# PowerRegulationBoardV2.net
KiCad netlist of a schematic drawn in Altium Designer
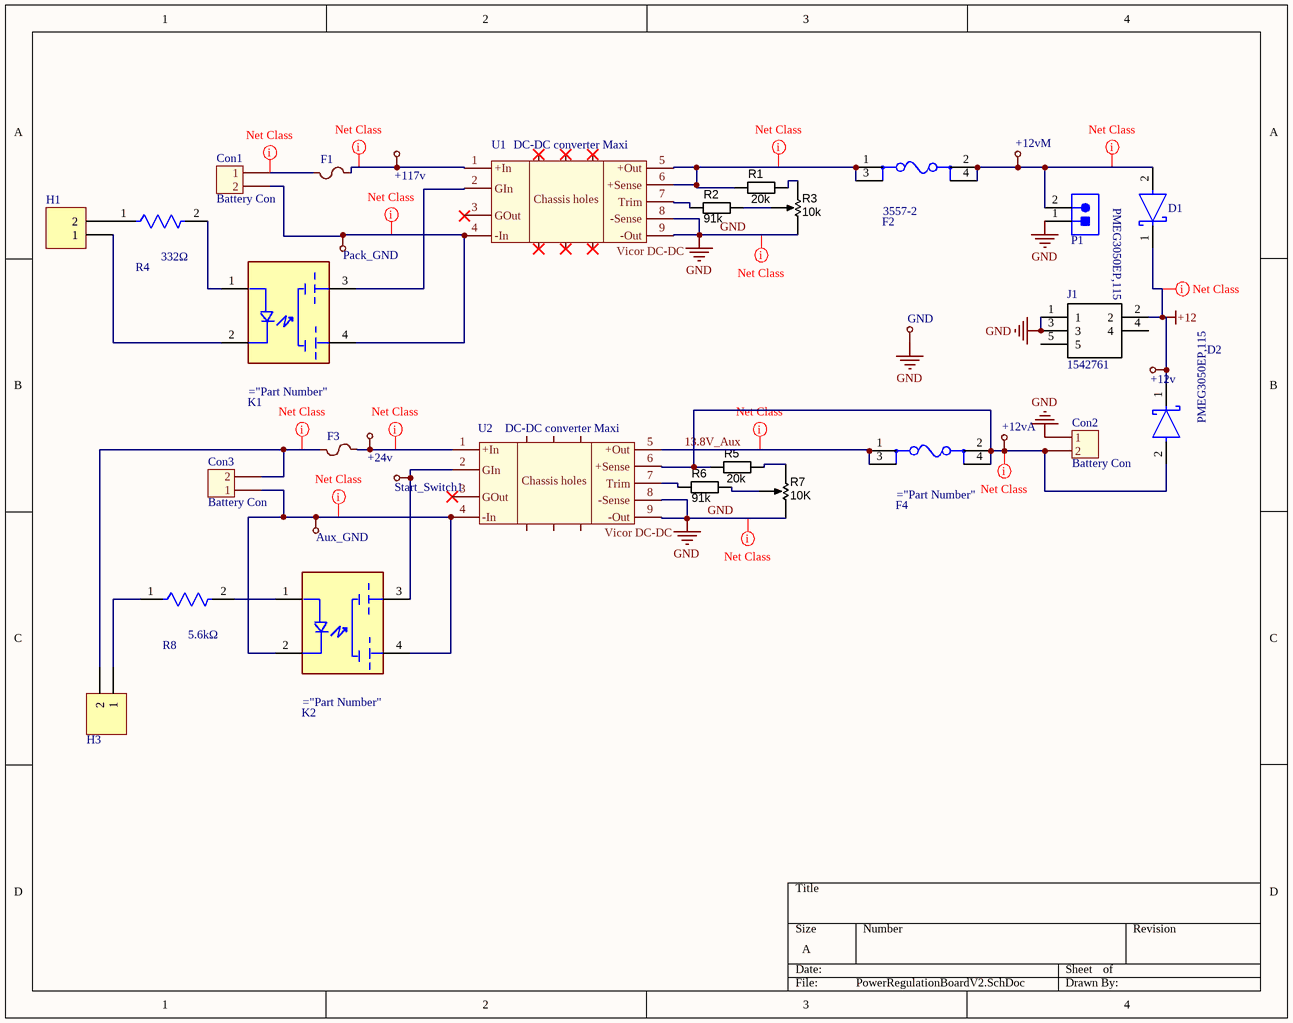
[diagram p0: PowerRegulationBoardV2.SchDoc]

(export (version "E")
  (design (tool "Eeschema 10.0.6"))
  (components
    (comp (ref "+12v")
      (value "Testpoint")
      (footprint "TestPoint")
      (libsource (lib "Components_library") (part "Testpoint"))
    )
    (comp (ref "+12vA")
      (value "Testpoint")
      (footprint "TestPoint")
      (libsource (lib "Components_library") (part "Testpoint"))
    )
    (comp (ref "+12vM")
      (value "Testpoint")
      (footprint "TestPoint")
      (libsource (lib "Components_library") (part "Testpoint"))
    )
    (comp (ref "+24v")
      (value "Testpoint")
      (footprint "TestPoint")
      (libsource (lib "Components_library") (part "Testpoint"))
    )
    (comp (ref "+117v")
      (value "Testpoint")
      (footprint "TestPoint")
      (libsource (lib "Components_library") (part "Testpoint"))
    )
    (comp (ref "Aux_GND")
      (value "Testpoint")
      (footprint "TestPoint")
      (libsource (lib "Components_library") (part "Testpoint"))
    )
    (comp (ref "Con1")
      (value "Battery Con")
      (footprint "Battery Con")
      (description "Aux and Main battery connector")
      (libsource (lib "") (part "Battery Con_1"))
    )
    (comp (ref "Con2")
      (value "Battery Con")
      (footprint "Battery Con")
      (description "Aux and Main battery connector")
      (libsource (lib "Components_library") (part "Battery Con"))
    )
    (comp (ref "Con3")
      (value "Battery Con")
      (footprint "Battery Con")
      (description "Aux and Main battery connector")
      (libsource (lib "") (part "Battery Con_1"))
    )
    (comp (ref "D1")
      (value "PMEG3050EP,115")
      (footprint "Nexperia_SOD128_0")
      (libsource (lib "Diode_Nexperia_PMEG3050EP,115_eec") (part "PMEG3050EP,115"))
    )
    (comp (ref "D2")
      (value "PMEG3050EP,115")
      (footprint "Nexperia_SOD128_0")
      (libsource (lib "Diode_Nexperia_PMEG3050EP,115_eec") (part "PMEG3050EP,115"))
    )
    (comp (ref "F1")
      (value "PC TRON Fuse 5A")
      (footprint "PC TRON 5A")
      (libsource (lib "Components_library") (part "PC TRON Fuse 5A"))
    )
    (comp (ref "F2")
      (value "3557-2")
      (footprint "Keystone_3557-2_0")
      (libsource (lib "Fuse_Keystone_3557-2_eec") (part "3557-2"))
    )
    (comp (ref "F3")
      (value "PC TRON Fuse 5A")
      (footprint "PC TRON 5A")
      (libsource (lib "Components_library") (part "PC TRON Fuse 5A"))
    )
    (comp (ref "F4")
      (value "3557-2")
      (footprint "Keystone_3557-2_0")
      (libsource (lib "Fuse_Keystone_3557-2_eec") (part "3557-2"))
    )
    (comp (ref "GND")
      (value "Testpoint")
      (footprint "TestPoint")
      (libsource (lib "Components_library") (part "Testpoint"))
    )
    (comp (ref "H1")
      (value "Header 0")
      (footprint "HDR1X2")
      (description "Header, 2-Pin")
      (fields (field (name "PUBLISHER") "Altium Limited"))
      (libsource (lib "") (part "Header 2_1"))
    )
    (comp (ref "H3")
      (value "Header 0")
      (footprint "HDR1X2")
      (description "Header, 2-Pin")
      (fields (field (name "PUBLISHER") "Altium Limited"))
      (libsource (lib "Miscellaneous Connectors") (part "Header 2"))
    )
    (comp (ref "J1")
      (value "1542761")
      (footprint "SamacSys:1542761")
      (description "Connector")
      (fields (field (name "MOUSER PART NUMBER") "651-1542761") (field (name "RS PART NUMBER") "8025583"))
      (libsource (lib "*") (part "1542761"))
    )
    (comp (ref "K1") (value "CPC1117N") (footprint "CPC1117N") (libsource (lib "CPC1117N") (part "CPC1117N")))
    (comp (ref "K2") (value "CPC1117N") (footprint "CPC1117N") (libsource (lib "CPC1117N") (part "CPC1117N")))
    (comp (ref "P1")
      (value "SCREW-5.0/5.08 2WAYS")
      (footprint "SCREW-5.0-2WAYS_V")
      (description "Socket, Screw Terminal Block, 2 Way, 5.0 mm Pitch, 90 Degree Angle, Through-Hole")
      (fields (field (name "MANUFACTURER") "No Vendor"))
      (libsource (lib "Altium Content Vault") (part "CMP-0617-00009-1"))
    )
    (comp (ref "Pack_GND")
      (value "Testpoint")
      (footprint "TestPoint")
      (libsource (lib "Components_library") (part "Testpoint"))
    )
    (comp (ref "R1")
      (value "20k")
      (footprint "Vishay_WSL2010_0")
      (description "RES SMD 20K OHM 1% 3/4W 2010")
      (fields (field (name "TOLERANCE") "±5%") (field (name "Comment") "Thick Film"))
      (libsource (lib "PBL - Resistors") (part "RES_10R_2010_5%"))
    )
    (comp (ref "R2")
      (value "91k")
      (footprint "Vishay_WSL2010_0")
      (description "RES SMD 91K OHM 5% 3/4W 2010 \r\n CRCW201091K0JNEF")
      (fields (field (name "TOLERANCE") "±5%") (field (name "Comment") "Thick Film"))
      (libsource (lib "PBL - Resistors") (part "RES_10R_2010_5%"))
    )
    (comp (ref "R3")
      (value "10k")
      (footprint "TrimPot_THT_2.54mm pitch")
      (description "TRIMMER 10K OHM 0.25W PC PIN TOP \r\n 64WR10KLF")
      (fields (field (name "TOLERANCE") "10%") (field (name "Comment") "25 Turn"))
      (libsource (lib "") (part "RES_TRIMMER_1K_25T_THT_1"))
    )
    (comp (ref "R4")
      (value "RK73H2BTTD3320F")
      (fields (field (name "PART NUMBER") "332Ω"))
      (libsource (lib "Res_KOA_Speer_RK73H2BTTD3320F_eec") (part "RK73H2BTTD3320F"))
    )
    (comp (ref "R5")
      (value "20k")
      (footprint "Vishay_WSL2010_0")
      (description "RES SMD 20K OHM 1% 3/4W 2010\r\n CRCW20101K20FKEF")
      (fields (field (name "TOLERANCE") "±5%") (field (name "Comment") "Thick Film"))
      (libsource (lib "PBL - Resistors") (part "RES_10R_2010_5%"))
    )
    (comp (ref "R6")
      (value "91k")
      (footprint "Vishay_WSL2010_0")
      (description "RES SMD 91K OHM 5% 3/4W 2010 \r\n CRCW201091K0JNEF")
      (fields (field (name "TOLERANCE") "±5%") (field (name "Comment") "Thick Film"))
      (libsource (lib "PBL - Resistors") (part "RES_10R_2010_5%"))
    )
    (comp (ref "R7")
      (value "10K")
      (footprint "TrimPot_THT_2.54mm pitch")
      (description "TRIMMER 10K OHM 0.25W PC PIN TOP \r\n 64WR10KLF")
      (fields (field (name "TOLERANCE") "10%") (field (name "Comment") "25 Turn"))
      (libsource (lib "PBL - Resistors") (part "RES_TRIMMER_1K_25T_THT"))
    )
    (comp (ref "R8")
      (value "CRCW12065K60FKEA")
      (footprint "Vishay_CRCW1206_IPC_A")
      (fields (field (name "PART NUMBER") "5.6kΩ"))
      (libsource (lib "Res_Vishay_CRCW12065K60FKEA_eec") (part "CRCW12065K60FKEA"))
    )
    (comp (ref "Start_Switch1")
      (value "Testpoint")
      (footprint "TestPoint")
      (libsource (lib "Components_library") (part "Testpoint"))
    )
    (comp (ref "U1")
      (value "DC-DC converter Maxi")
      (footprint "Vicor DC-DC Maxi")
      (libsource (lib "Components_library") (part "DC-DC converter Maxi"))
    )
    (comp (ref "U2")
      (value "DC-DC converter Maxi")
      (footprint "Vicor DC-DC Maxi")
      (libsource (lib "Components_library") (part "DC-DC converter Maxi"))
    )
  )
  (nets
    (net (code "1") (name "+12") (class "Default")
      (node (ref "+12v") (pin "1") (pinfunction "1_1") (pintype "passive"))
      (node (ref "D1") (pin "1") (pinfunction "C_1") (pintype "passive"))
      (node (ref "D2") (pin "1") (pinfunction "C_1") (pintype "passive"))
      (node (ref "J1") (pin "2") (pinfunction "2_2") (pintype "passive"))
    )
    (net (code "2") (name "/13.8V_Aux") (class "Default")
      (node (ref "F4") (pin "1") (pinfunction "1_1") (pintype "passive"))
      (node (ref "F4") (pin "3") (pinfunction "3_3") (pintype "passive"))
      (node (ref "U2") (pin "5") (pinfunction "+Out_5") (pintype "power_in"))
    )
    (net (code "3") (name "GND") (class "Default")
      (node (ref "Con2") (pin "1") (pinfunction "1_1") (pintype "passive"))
      (node (ref "GND") (pin "1") (pinfunction "1_1") (pintype "passive"))
      (node (ref "J1") (pin "1") (pinfunction "1_1") (pintype "passive"))
      (node (ref "J1") (pin "3") (pinfunction "3_3") (pintype "passive"))
      (node (ref "P1") (pin "1") (pinfunction "1_1") (pintype "passive"))
      (node (ref "R3") (pin "1") (pinfunction "CW_1") (pintype "passive"))
      (node (ref "R7") (pin "3") (pinfunction "CW_3") (pintype "passive"))
      (node (ref "U1") (pin "8") (pinfunction "-Sense_8") (pintype "power_in"))
      (node (ref "U1") (pin "9") (pinfunction "-Out_9") (pintype "power_in"))
      (node (ref "U2") (pin "8") (pinfunction "-Sense_8") (pintype "power_in"))
      (node (ref "U2") (pin "9") (pinfunction "-Out_9") (pintype "power_in"))
    )
    (net (code "4") (name "Net-(Con1-1)") (class "Default")
      (node (ref "Con1") (pin "2") (pinfunction "1_2") (pintype "passive"))
      (node (ref "F1") (pin "1") (pinfunction "1_1") (pintype "passive"))
    )
    (net (code "5") (name "Net-(Con1-2)") (class "Default")
      (node (ref "Con1") (pin "1") (pinfunction "2_1") (pintype "passive"))
      (node (ref "K1") (pin "4") (pinfunction "DRAIN_4") (pintype "passive"))
      (node (ref "Pack_GND") (pin "1") (pinfunction "1_1") (pintype "passive"))
      (node (ref "U1") (pin "4") (pinfunction "-In_4") (pintype "power_in"))
    )
    (net (code "6") (name "Net-(Con3-1)") (class "Default")
      (node (ref "Con3") (pin "2") (pinfunction "1_2") (pintype "passive"))
      (node (ref "F3") (pin "1") (pinfunction "1_1") (pintype "passive"))
      (node (ref "H3") (pin "2") (pinfunction "2_2") (pintype "passive"))
    )
    (net (code "7") (name "Net-(Con3-2)") (class "Default")
      (node (ref "Aux_GND") (pin "1") (pinfunction "1_1") (pintype "passive"))
      (node (ref "Con3") (pin "1") (pinfunction "2_1") (pintype "passive"))
      (node (ref "K2") (pin "2") (pinfunction "C_2") (pintype "passive"))
      (node (ref "K2") (pin "4") (pinfunction "DRAIN_4") (pintype "passive"))
      (node (ref "U2") (pin "4") (pinfunction "-In_4") (pintype "power_in"))
    )
    (net (code "8") (name "Net-(D1-A)") (class "Default")
      (node (ref "+12vM") (pin "1") (pinfunction "1_1") (pintype "passive"))
      (node (ref "D1") (pin "2") (pinfunction "A_2") (pintype "passive"))
      (node (ref "F2") (pin "2") (pinfunction "2_2") (pintype "passive"))
      (node (ref "F2") (pin "4") (pinfunction "4_4") (pintype "passive"))
      (node (ref "P1") (pin "2") (pinfunction "2_2") (pintype "passive"))
    )
    (net (code "9") (name "Net-(D2-A)") (class "Default")
      (node (ref "+12vA") (pin "1") (pinfunction "1_1") (pintype "passive"))
      (node (ref "Con2") (pin "2") (pinfunction "2_2") (pintype "passive"))
      (node (ref "D2") (pin "2") (pinfunction "A_2") (pintype "passive"))
      (node (ref "F4") (pin "2") (pinfunction "2_2") (pintype "passive"))
      (node (ref "F4") (pin "4") (pinfunction "4_4") (pintype "passive"))
      (node (ref "R5") (pin "2") (pinfunction "2_2") (pintype "passive"))
      (node (ref "U2") (pin "6") (pinfunction "+Sense_6") (pintype "power_in"))
    )
    (net (code "10") (name "Net-(H1-Pad2)") (class "Default")
      (node (ref "H1") (pin "2") (pinfunction "2_2") (pintype "passive"))
      (node (ref "R4") (pin "1") (pinfunction "1_1") (pintype "passive"))
    )
    (net (code "11") (name "Net-(H3-Pad1)") (class "Default")
      (node (ref "H3") (pin "1") (pinfunction "1_1") (pintype "passive"))
      (node (ref "R8") (pin "1") (pinfunction "1_1") (pintype "passive"))
    )
    (net (code "12") (name "Net-(K1-A)") (class "Default")
      (node (ref "K1") (pin "1") (pinfunction "A_1") (pintype "passive"))
      (node (ref "R4") (pin "2") (pinfunction "2_2") (pintype "passive"))
    )
    (net (code "13") (name "Net-(K1-C)") (class "Default")
      (node (ref "H1") (pin "1") (pinfunction "1_1") (pintype "passive"))
      (node (ref "K1") (pin "2") (pinfunction "C_2") (pintype "passive"))
    )
    (net (code "14") (name "Net-(K2-A)") (class "Default")
      (node (ref "K2") (pin "1") (pinfunction "A_1") (pintype "passive"))
      (node (ref "R8") (pin "2") (pinfunction "2_2") (pintype "passive"))
    )
    (net (code "15") (name "Net-(R3-CCW)") (class "Default")
      (node (ref "R1") (pin "1") (pinfunction "1_1") (pintype "passive"))
      (node (ref "R3") (pin "3") (pinfunction "CCW_3") (pintype "passive"))
    )
    (net (code "16") (name "Net-(R3-TAP)") (class "Default")
      (node (ref "R2") (pin "1") (pinfunction "1_1") (pintype "passive"))
      (node (ref "R3") (pin "2") (pinfunction "TAP_2") (pintype "passive"))
    )
    (net (code "17") (name "Net-(R7-CCW)") (class "Default")
      (node (ref "R5") (pin "1") (pinfunction "1_1") (pintype "passive"))
      (node (ref "R7") (pin "1") (pinfunction "CCW_1") (pintype "passive"))
    )
    (net (code "18") (name "Net-(R7-TAP)") (class "Default")
      (node (ref "R6") (pin "1") (pinfunction "1_1") (pintype "passive"))
      (node (ref "R7") (pin "2") (pinfunction "TAP_2") (pintype "passive"))
    )
    (net (code "19") (name "Net-(U1-+In)") (class "Default")
      (node (ref "+117v") (pin "1") (pinfunction "1_1") (pintype "passive"))
      (node (ref "F1") (pin "2") (pinfunction "2_2") (pintype "passive"))
      (node (ref "U1") (pin "1") (pinfunction "+In_1") (pintype "power_in"))
    )
    (net (code "20") (name "Net-(U1-+Out)") (class "Default")
      (node (ref "F2") (pin "1") (pinfunction "1_1") (pintype "passive"))
      (node (ref "F2") (pin "3") (pinfunction "3_3") (pintype "passive"))
      (node (ref "R1") (pin "2") (pinfunction "2_2") (pintype "passive"))
      (node (ref "U1") (pin "5") (pinfunction "+Out_5") (pintype "power_in"))
      (node (ref "U1") (pin "6") (pinfunction "+Sense_6") (pintype "power_in"))
    )
    (net (code "21") (name "Net-(U1-GIn)") (class "Default")
      (node (ref "K1") (pin "3") (pinfunction "DRAIN_3") (pintype "passive"))
      (node (ref "U1") (pin "2") (pinfunction "GIn_2") (pintype "power_in"))
    )
    (net (code "22") (name "Net-(U1-Trim)") (class "Default")
      (node (ref "R2") (pin "2") (pinfunction "2_2") (pintype "passive"))
      (node (ref "U1") (pin "7") (pinfunction "Trim_7") (pintype "power_in"))
    )
    (net (code "23") (name "Net-(U2-+In)") (class "Default")
      (node (ref "+24v") (pin "1") (pinfunction "1_1") (pintype "passive"))
      (node (ref "F3") (pin "2") (pinfunction "2_2") (pintype "passive"))
      (node (ref "U2") (pin "1") (pinfunction "+In_1") (pintype "power_in"))
    )
    (net (code "24") (name "Net-(U2-GIn)") (class "Default")
      (node (ref "K2") (pin "3") (pinfunction "DRAIN_3") (pintype "passive"))
      (node (ref "Start_Switch1") (pin "1") (pinfunction "1_1") (pintype "passive"))
      (node (ref "U2") (pin "2") (pinfunction "GIn_2") (pintype "power_in"))
    )
    (net (code "25") (name "Net-(U2-Trim)") (class "Default")
      (node (ref "R6") (pin "2") (pinfunction "2_2") (pintype "passive"))
      (node (ref "U2") (pin "7") (pinfunction "Trim_7") (pintype "power_in"))
    )
    (net (code "26") (name "unconnected-(J1-Pad4)") (class "Default")
      (node (ref "J1") (pin "4") (pinfunction "4_4") (pintype "passive"))
    )
    (net (code "27") (name "unconnected-(J1-Pad5)") (class "Default")
      (node (ref "J1") (pin "5") (pinfunction "5_5") (pintype "passive"))
    )
    (net (code "28") (name "unconnected-(U1-10-Pad11)") (class "Default")
      (node (ref "U1") (pin "11") (pinfunction "10_11") (pintype "passive+no_connect"))
    )
    (net (code "29") (name "unconnected-(U1-GOut-Pad3)") (class "Default")
      (node (ref "U1") (pin "3") (pinfunction "GOut_3") (pintype "power_in"))
    )
    (net (code "30") (name "unconnected-(U1-Pad11)") (class "Default")
      (node (ref "U1") (pin "11") (pinfunction "11_11") (pintype "passive+no_connect"))
    )
    (net (code "31") (name "unconnected-(U1-Pad12)") (class "Default")
      (node (ref "U1") (pin "12") (pinfunction "12_12") (pintype "passive+no_connect"))
    )
    (net (code "32") (name "unconnected-(U1-Pad13)") (class "Default")
      (node (ref "U1") (pin "13") (pinfunction "13_13") (pintype "passive+no_connect"))
    )
    (net (code "33") (name "unconnected-(U1-Pad14)") (class "Default")
      (node (ref "U1") (pin "14") (pinfunction "14_14") (pintype "passive+no_connect"))
    )
    (net (code "34") (name "unconnected-(U1-Pad15)") (class "Default")
      (node (ref "U1") (pin "15") (pinfunction "15_15") (pintype "passive+no_connect"))
    )
    (net (code "35") (name "unconnected-(U2-10-Pad11)") (class "Default")
      (node (ref "U2") (pin "11") (pinfunction "10_11") (pintype "passive"))
    )
    (net (code "36") (name "unconnected-(U2-GOut-Pad3)") (class "Default")
      (node (ref "U2") (pin "3") (pinfunction "GOut_3") (pintype "power_in+no_connect"))
    )
    (net (code "37") (name "unconnected-(U2-Pad11)") (class "Default")
      (node (ref "U2") (pin "11") (pinfunction "11_11") (pintype "passive"))
    )
    (net (code "38") (name "unconnected-(U2-Pad12)") (class "Default")
      (node (ref "U2") (pin "12") (pinfunction "12_12") (pintype "passive"))
    )
    (net (code "39") (name "unconnected-(U2-Pad13)") (class "Default")
      (node (ref "U2") (pin "13") (pinfunction "13_13") (pintype "passive"))
    )
    (net (code "40") (name "unconnected-(U2-Pad14)") (class "Default")
      (node (ref "U2") (pin "14") (pinfunction "14_14") (pintype "passive"))
    )
    (net (code "41") (name "unconnected-(U2-Pad15)") (class "Default")
      (node (ref "U2") (pin "15") (pinfunction "15_15") (pintype "passive"))
    )
  )
)
